# PiHAT_SSR_V4.net
KiCad netlist of a schematic drawn in EAGLE
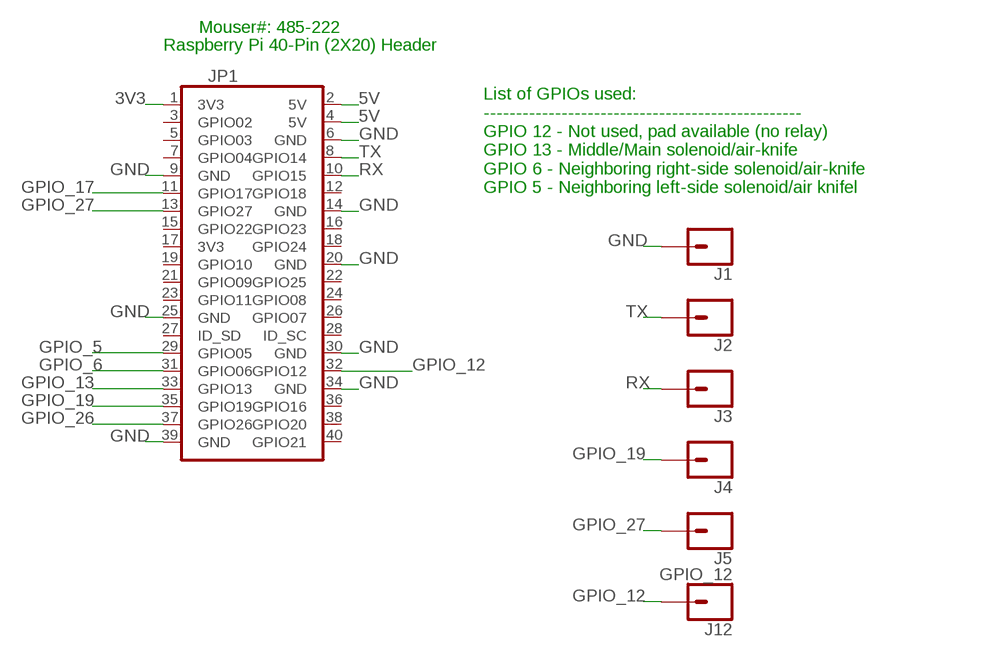
[diagram p0: schematic, sheet 1]
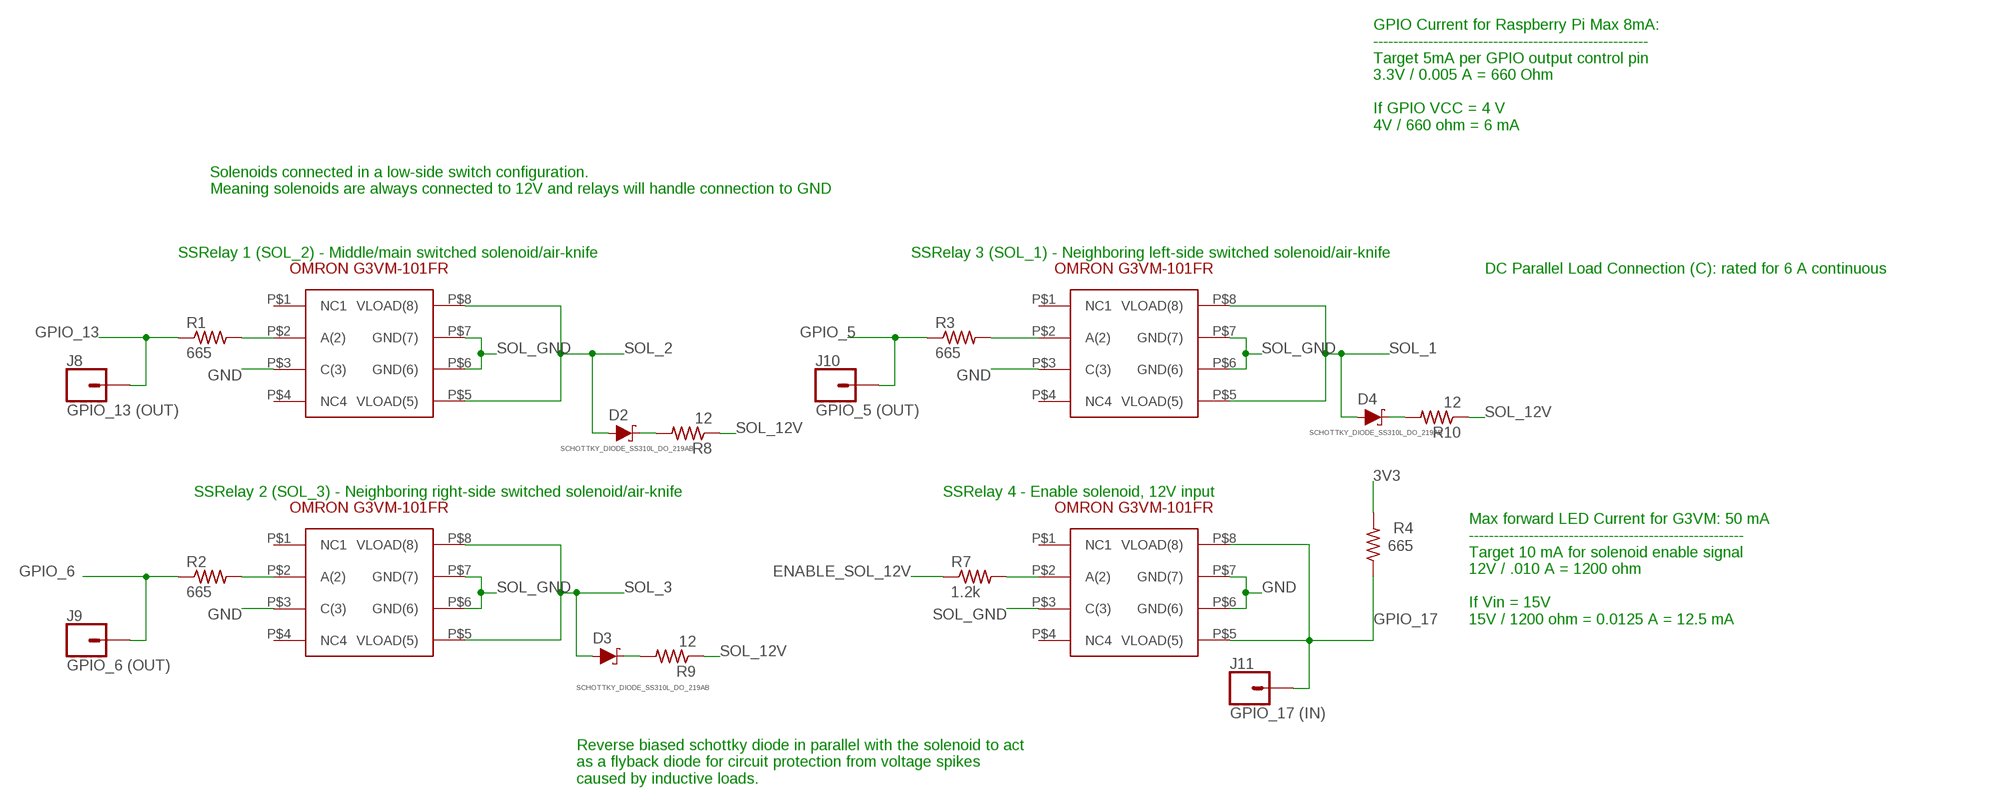
[diagram p1: schematic, sheet 2]
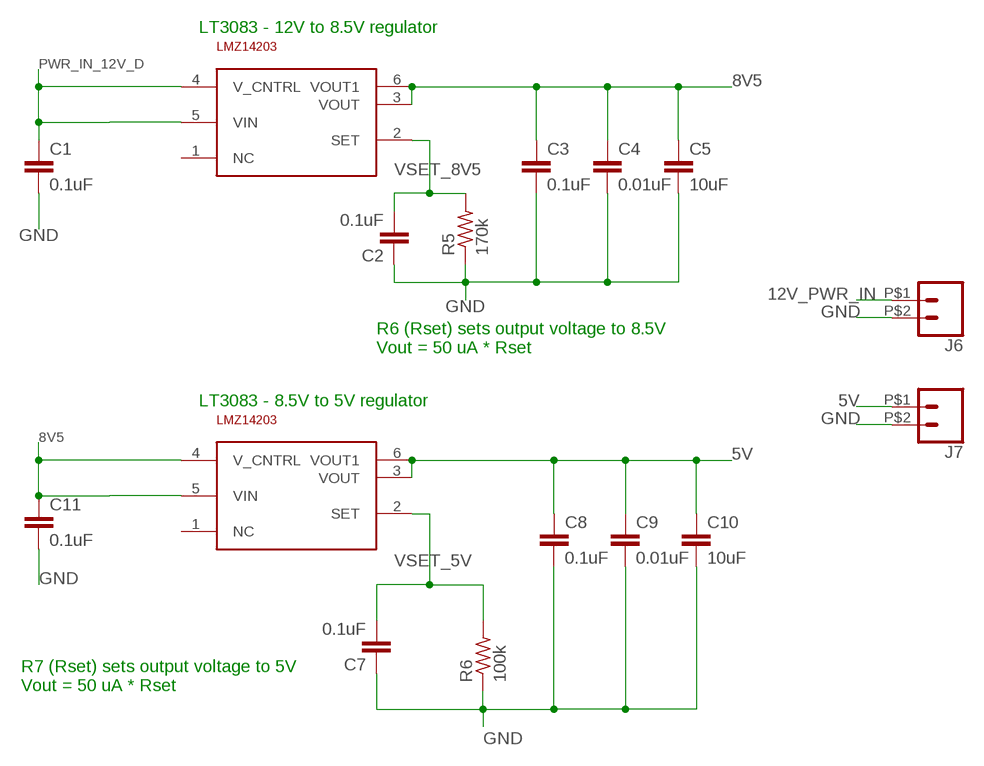
[diagram p2: schematic, sheet 3]
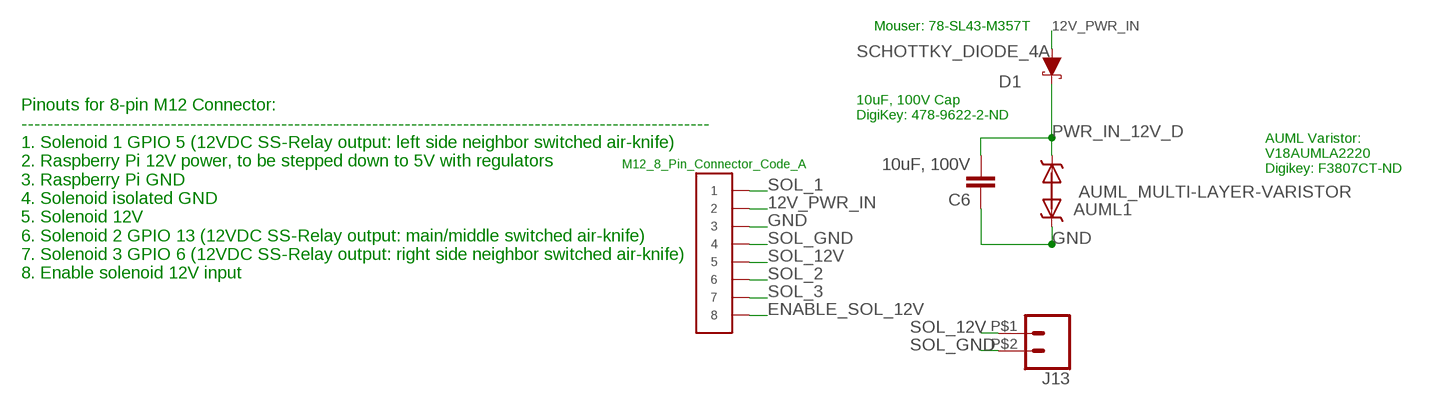
[diagram p3: schematic, sheet 4]

(export (version "E")
  (design (tool "Eeschema 10.0.6"))
  (components
    (comp (ref "C1")
      (value "0.1uF")
      (footprint "eagle-import:C0805")
      (libsource (lib "eagle-import") (part "C-EUC0805"))
    )
    (comp (ref "C2")
      (value "0.1uF")
      (footprint "eagle-import:C0805")
      (libsource (lib "eagle-import") (part "C-EUC0805"))
    )
    (comp (ref "C3")
      (value "0.1uF")
      (footprint "eagle-import:C0805")
      (libsource (lib "eagle-import") (part "C-EUC0805"))
    )
    (comp (ref "C4")
      (value "0.01uF")
      (footprint "eagle-import:C0805")
      (libsource (lib "eagle-import") (part "C-EUC0805"))
    )
    (comp (ref "C5")
      (value "10uF")
      (footprint "eagle-import:C0805")
      (libsource (lib "eagle-import") (part "C-EUC0805"))
    )
    (comp (ref "C7")
      (value "0.1uF")
      (footprint "eagle-import:C0805")
      (libsource (lib "eagle-import") (part "C-EUC0805"))
    )
    (comp (ref "C8")
      (value "0.1uF")
      (footprint "eagle-import:C0805")
      (libsource (lib "eagle-import") (part "C-EUC0805"))
    )
    (comp (ref "C9")
      (value "0.01uF")
      (footprint "eagle-import:C0805")
      (libsource (lib "eagle-import") (part "C-EUC0805"))
    )
    (comp (ref "C10")
      (value "10uF")
      (footprint "eagle-import:C0805")
      (libsource (lib "eagle-import") (part "C-EUC0805"))
    )
    (comp (ref "C11")
      (value "0.1uF")
      (footprint "eagle-import:C0805")
      (libsource (lib "eagle-import") (part "C-EUC0805"))
    )
    (comp (ref "J6")
      (value "CONN_02PTH2")
      (footprint "eagle-import:1X02_BIG")
      (libsource (lib "eagle-import") (part "CONN_02PTH2"))
    )
    (comp (ref "J7")
      (value "CONN_02PTH2")
      (footprint "eagle-import:1X02_BIG")
      (libsource (lib "eagle-import") (part "CONN_02PTH2"))
    )
    (comp (ref "R5")
      (value "170k")
      (footprint "eagle-import:M0805")
      (libsource (lib "eagle-import") (part "R-US_M0805"))
    )
    (comp (ref "R6")
      (value "100k")
      (footprint "eagle-import:M0805")
      (libsource (lib "eagle-import") (part "R-US_M0805"))
    )
    (comp (ref "VR1")
      (value "SMD-SPECIAL_28PIN_PIC32_11_3_2011_LT3083")
      (footprint "eagle-import:SMD-SPECIAL_28PIN_PIC32_11_3_2011_DPAK-5")
      (libsource (lib "eagle-import") (part "SMD-SPECIAL_28PIN_PIC32_11_3_2011_LT3083"))
    )
    (comp (ref "VR2")
      (value "SMD-SPECIAL_28PIN_PIC32_11_3_2011_LT3083")
      (footprint "eagle-import:SMD-SPECIAL_28PIN_PIC32_11_3_2011_DPAK-5")
      (libsource (lib "eagle-import") (part "SMD-SPECIAL_28PIN_PIC32_11_3_2011_LT3083"))
    )
    (comp (ref "J1")
      (value "CONN_01")
      (footprint "eagle-import:1X01")
      (libsource (lib "eagle-import") (part "CONN_01"))
    )
    (comp (ref "J2")
      (value "CONN_01")
      (footprint "eagle-import:1X01")
      (libsource (lib "eagle-import") (part "CONN_01"))
    )
    (comp (ref "J3")
      (value "CONN_01")
      (footprint "eagle-import:1X01")
      (libsource (lib "eagle-import") (part "CONN_01"))
    )
    (comp (ref "J4")
      (value "CONN_01")
      (footprint "eagle-import:1X01")
      (libsource (lib "eagle-import") (part "CONN_01"))
    )
    (comp (ref "J5")
      (value "CONN_01")
      (footprint "eagle-import:1X01")
      (libsource (lib "eagle-import") (part "CONN_01"))
    )
    (comp (ref "J12")
      (value "GPIO_12")
      (footprint "eagle-import:1X01")
      (libsource (lib "eagle-import") (part "CONN_01"))
    )
    (comp (ref "JP1")
      (value "40W_PI_HAT_TPH")
      (footprint "eagle-import:2X20")
      (libsource (lib "eagle-import") (part "40W_PI_HAT_TPH"))
    )
    (comp (ref "D2")
      (value "SCHOTTKY_DIODE_SS310L_DO_219AB")
      (footprint "eagle-import:SCHOTTKY_DIODE_DO219AB")
      (libsource (lib "eagle-import") (part "SCHOTTKY_DIODE_SS310L_DO_219AB"))
    )
    (comp (ref "D3")
      (value "SCHOTTKY_DIODE_SS310L_DO_219AB")
      (footprint "eagle-import:SCHOTTKY_DIODE_DO219AB")
      (libsource (lib "eagle-import") (part "SCHOTTKY_DIODE_SS310L_DO_219AB"))
    )
    (comp (ref "D4")
      (value "SCHOTTKY_DIODE_SS310L_DO_219AB")
      (footprint "eagle-import:SCHOTTKY_DIODE_DO219AB")
      (libsource (lib "eagle-import") (part "SCHOTTKY_DIODE_SS310L_DO_219AB"))
    )
    (comp (ref "J8")
      (value "GPIO_13 (OUT)")
      (footprint "eagle-import:1X01")
      (libsource (lib "eagle-import") (part "CONN_01"))
    )
    (comp (ref "J9")
      (value "GPIO_6 (OUT)")
      (footprint "eagle-import:1X01")
      (libsource (lib "eagle-import") (part "CONN_01"))
    )
    (comp (ref "J10")
      (value "GPIO_5 (OUT)")
      (footprint "eagle-import:1X01")
      (libsource (lib "eagle-import") (part "CONN_01"))
    )
    (comp (ref "J11")
      (value "GPIO_17 (IN)")
      (footprint "eagle-import:1X01")
      (libsource (lib "eagle-import") (part "CONN_01"))
    )
    (comp (ref "R1")
      (value "665")
      (footprint "eagle-import:M0805")
      (libsource (lib "eagle-import") (part "R-US_M0805"))
    )
    (comp (ref "R2")
      (value "665")
      (footprint "eagle-import:M0805")
      (libsource (lib "eagle-import") (part "R-US_M0805"))
    )
    (comp (ref "R3")
      (value "665")
      (footprint "eagle-import:M0805")
      (libsource (lib "eagle-import") (part "R-US_M0805"))
    )
    (comp (ref "R4")
      (value "665")
      (footprint "eagle-import:M0805")
      (libsource (lib "eagle-import") (part "R-US_M0805"))
    )
    (comp (ref "R7")
      (value "1.2k")
      (footprint "eagle-import:M0805")
      (libsource (lib "eagle-import") (part "R-US_M0805"))
    )
    (comp (ref "R8")
      (value "12")
      (footprint "eagle-import:R1210")
      (libsource (lib "eagle-import") (part "R-US_R1210"))
    )
    (comp (ref "R9")
      (value "12")
      (footprint "eagle-import:R1210")
      (libsource (lib "eagle-import") (part "R-US_R1210"))
    )
    (comp (ref "R10")
      (value "12")
      (footprint "eagle-import:R1210")
      (libsource (lib "eagle-import") (part "R-US_R1210"))
    )
    (comp (ref "SSR1")
      (value "OMRON_G3VM_101FR")
      (footprint "eagle-import:OMRON_G3VM-101FR")
      (libsource (lib "eagle-import") (part "OMRON_G3VM_101FR"))
    )
    (comp (ref "SSR2")
      (value "OMRON_G3VM_101FR")
      (footprint "eagle-import:OMRON_G3VM-101FR")
      (libsource (lib "eagle-import") (part "OMRON_G3VM_101FR"))
    )
    (comp (ref "SSR3")
      (value "OMRON_G3VM_101FR")
      (footprint "eagle-import:OMRON_G3VM-101FR")
      (libsource (lib "eagle-import") (part "OMRON_G3VM_101FR"))
    )
    (comp (ref "SSR4")
      (value "OMRON_G3VM_101FR")
      (footprint "eagle-import:OMRON_G3VM-101FR")
      (libsource (lib "eagle-import") (part "OMRON_G3VM_101FR"))
    )
    (comp (ref "AUML1")
      (value "SMD-SPECIAL_28PIN_PIC32_11_3_2011_MOD5_20_13_AUML_MULTI-LAYER-VARISTOR")
      (footprint "eagle-import:SMD-SPECIAL_28PIN_PIC32_11_3_2011_MOD5_20_13_SMT_CAP_2220")
      (libsource (lib "eagle-import") (part "SMD-SPECIAL_28PIN_PIC32_11_3_2011_MOD5_20_13_AUML_MULTI-LAYER-VARISTOR"))
    )
    (comp (ref "C6")
      (value "10uF, 100V")
      (footprint "eagle-import:C2220K")
      (libsource (lib "eagle-import") (part "C-EUC2220K"))
    )
    (comp (ref "CN1")
      (value "M12_8PIN_CODE_A")
      (footprint "eagle-import:M12_8PIN_CODE_A")
      (libsource (lib "eagle-import") (part "M12_8PIN_CODE_A"))
    )
    (comp (ref "D1")
      (value "SCHOTTKY_DIODE_4A")
      (footprint "eagle-import:SCHOTTKY_DIODE_SMD_DO-214AB")
      (libsource (lib "eagle-import") (part "SCHOTTKY_DIODE_4A"))
    )
    (comp (ref "J13")
      (value "CONN_02PTH2")
      (footprint "eagle-import:1X02_BIG")
      (libsource (lib "eagle-import") (part "CONN_02PTH2"))
    )
  )
  (nets
    (net (code "1") (name "3V3") (class "Default")
      (node (ref "JP1") (pin "1") (pinfunction "3V3_1") (pintype "passive"))
      (node (ref "R4") (pin "2") (pinfunction "2_2") (pintype "passive"))
    )
    (net (code "2") (name "5V") (class "Default")
      (node (ref "C10") (pin "1") (pinfunction "1_1") (pintype "passive"))
      (node (ref "C8") (pin "1") (pinfunction "1_1") (pintype "passive"))
      (node (ref "C9") (pin "1") (pinfunction "1_1") (pintype "passive"))
      (node (ref "J7") (pin "P$1") (pinfunction "1_P$1") (pintype "passive"))
      (node (ref "JP1") (pin "2") (pinfunction "5V_2") (pintype "passive"))
      (node (ref "JP1") (pin "4") (pinfunction "5V_4") (pintype "passive"))
      (node (ref "VR2") (pin "3") (pinfunction "VOUT_3") (pintype "bidirectional"))
      (node (ref "VR2") (pin "6") (pinfunction "VOUT1_6") (pintype "bidirectional"))
    )
    (net (code "3") (name "8V5") (class "Default")
      (node (ref "C11") (pin "1") (pinfunction "1_1") (pintype "passive"))
      (node (ref "C3") (pin "1") (pinfunction "1_1") (pintype "passive"))
      (node (ref "C4") (pin "1") (pinfunction "1_1") (pintype "passive"))
      (node (ref "C5") (pin "1") (pinfunction "1_1") (pintype "passive"))
      (node (ref "VR1") (pin "3") (pinfunction "VOUT_3") (pintype "bidirectional"))
      (node (ref "VR1") (pin "6") (pinfunction "VOUT1_6") (pintype "bidirectional"))
      (node (ref "VR2") (pin "4") (pinfunction "V_CNTRL_4") (pintype "bidirectional"))
      (node (ref "VR2") (pin "5") (pinfunction "VIN_5") (pintype "bidirectional"))
    )
    (net (code "4") (name "12V_PWR_IN") (class "Default")
      (node (ref "CN1") (pin "P$2") (pinfunction "P$2_P$2") (pintype "bidirectional"))
      (node (ref "D1") (pin "P$2") (pinfunction "A_P$2") (pintype "passive"))
      (node (ref "J6") (pin "P$1") (pinfunction "1_P$1") (pintype "passive"))
    )
    (net (code "5") (name "ENABLE_SOL_12V") (class "Default")
      (node (ref "CN1") (pin "P$8") (pinfunction "P$8_P$8") (pintype "bidirectional"))
      (node (ref "R7") (pin "1") (pinfunction "1_1") (pintype "passive"))
    )
    (net (code "6") (name "GND") (class "Default")
      (node (ref "AUML1") (pin "1") (pinfunction "1_1") (pintype "passive"))
      (node (ref "C1") (pin "2") (pinfunction "2_2") (pintype "passive"))
      (node (ref "C10") (pin "2") (pinfunction "2_2") (pintype "passive"))
      (node (ref "C11") (pin "2") (pinfunction "2_2") (pintype "passive"))
      (node (ref "C2") (pin "1") (pinfunction "1_1") (pintype "passive"))
      (node (ref "C3") (pin "2") (pinfunction "2_2") (pintype "passive"))
      (node (ref "C4") (pin "2") (pinfunction "2_2") (pintype "passive"))
      (node (ref "C5") (pin "2") (pinfunction "2_2") (pintype "passive"))
      (node (ref "C6") (pin "1") (pinfunction "1_1") (pintype "passive"))
      (node (ref "C7") (pin "1") (pinfunction "1_1") (pintype "passive"))
      (node (ref "C8") (pin "2") (pinfunction "2_2") (pintype "passive"))
      (node (ref "C9") (pin "2") (pinfunction "2_2") (pintype "passive"))
      (node (ref "CN1") (pin "P$3") (pinfunction "P$3_P$3") (pintype "bidirectional"))
      (node (ref "J1") (pin "1") (pinfunction "1_1") (pintype "passive"))
      (node (ref "J6") (pin "P$2") (pinfunction "2_P$2") (pintype "passive"))
      (node (ref "J7") (pin "P$2") (pinfunction "2_P$2") (pintype "passive"))
      (node (ref "JP1") (pin "14") (pinfunction "GND_14") (pintype "passive"))
      (node (ref "JP1") (pin "20") (pinfunction "GND_20") (pintype "passive"))
      (node (ref "JP1") (pin "25") (pinfunction "GND_25") (pintype "passive"))
      (node (ref "JP1") (pin "30") (pinfunction "GND_30") (pintype "passive"))
      (node (ref "JP1") (pin "34") (pinfunction "GND_34") (pintype "passive"))
      (node (ref "JP1") (pin "39") (pinfunction "GND_39") (pintype "passive"))
      (node (ref "JP1") (pin "6") (pinfunction "GND_6") (pintype "passive"))
      (node (ref "JP1") (pin "9") (pinfunction "GND_9") (pintype "passive"))
      (node (ref "R5") (pin "1") (pinfunction "1_1") (pintype "passive"))
      (node (ref "R6") (pin "1") (pinfunction "1_1") (pintype "passive"))
      (node (ref "SSR1") (pin "P$3") (pinfunction "C(3)_P$3") (pintype "bidirectional"))
      (node (ref "SSR2") (pin "P$3") (pinfunction "C(3)_P$3") (pintype "bidirectional"))
      (node (ref "SSR3") (pin "P$3") (pinfunction "C(3)_P$3") (pintype "bidirectional"))
      (node (ref "SSR4") (pin "P$6") (pinfunction "GND(6)_P$6") (pintype "bidirectional"))
      (node (ref "SSR4") (pin "P$7") (pinfunction "GND(7)_P$7") (pintype "bidirectional"))
    )
    (net (code "7") (name "GPIO_5") (class "Default")
      (node (ref "J10") (pin "1") (pinfunction "1_1") (pintype "passive"))
      (node (ref "JP1") (pin "29") (pinfunction "GPIO05_29") (pintype "passive"))
      (node (ref "R3") (pin "1") (pinfunction "1_1") (pintype "passive"))
    )
    (net (code "8") (name "GPIO_6") (class "Default")
      (node (ref "J9") (pin "1") (pinfunction "1_1") (pintype "passive"))
      (node (ref "JP1") (pin "31") (pinfunction "GPIO06_31") (pintype "passive"))
      (node (ref "R2") (pin "1") (pinfunction "1_1") (pintype "passive"))
    )
    (net (code "9") (name "GPIO_12") (class "Default")
      (node (ref "J12") (pin "1") (pinfunction "1_1") (pintype "passive"))
      (node (ref "JP1") (pin "32") (pinfunction "GPIO12_32") (pintype "passive"))
    )
    (net (code "10") (name "GPIO_13") (class "Default")
      (node (ref "J8") (pin "1") (pinfunction "1_1") (pintype "passive"))
      (node (ref "JP1") (pin "33") (pinfunction "GPIO13_33") (pintype "passive"))
      (node (ref "R1") (pin "1") (pinfunction "1_1") (pintype "passive"))
    )
    (net (code "11") (name "GPIO_17") (class "Default")
      (node (ref "J11") (pin "1") (pinfunction "1_1") (pintype "passive"))
      (node (ref "JP1") (pin "11") (pinfunction "GPIO17_11") (pintype "passive"))
      (node (ref "R4") (pin "1") (pinfunction "1_1") (pintype "passive"))
      (node (ref "SSR4") (pin "P$5") (pinfunction "VLOAD(5)_P$5") (pintype "bidirectional"))
      (node (ref "SSR4") (pin "P$8") (pinfunction "VLOAD(8)_P$8") (pintype "bidirectional"))
    )
    (net (code "12") (name "GPIO_19") (class "Default")
      (node (ref "J4") (pin "1") (pinfunction "1_1") (pintype "passive"))
      (node (ref "JP1") (pin "35") (pinfunction "GPIO19_35") (pintype "passive"))
    )
    (net (code "13") (name "GPIO_26") (class "Default")
      (node (ref "JP1") (pin "37") (pinfunction "GPIO26_37") (pintype "passive"))
    )
    (net (code "14") (name "GPIO_27") (class "Default")
      (node (ref "J5") (pin "1") (pinfunction "1_1") (pintype "passive"))
      (node (ref "JP1") (pin "13") (pinfunction "GPIO27_13") (pintype "passive"))
    )
    (net (code "15") (name "Net-(D2-C)") (class "Default")
      (node (ref "D2") (pin "P$2") (pinfunction "C_P$2") (pintype "passive"))
      (node (ref "R8") (pin "2") (pinfunction "2_2") (pintype "passive"))
    )
    (net (code "16") (name "Net-(D3-C)") (class "Default")
      (node (ref "D3") (pin "P$2") (pinfunction "C_P$2") (pintype "passive"))
      (node (ref "R9") (pin "2") (pinfunction "2_2") (pintype "passive"))
    )
    (net (code "17") (name "Net-(D4-C)") (class "Default")
      (node (ref "D4") (pin "P$2") (pinfunction "C_P$2") (pintype "passive"))
      (node (ref "R10") (pin "2") (pinfunction "2_2") (pintype "passive"))
    )
    (net (code "18") (name "Net-(SSR1-A(2))") (class "Default")
      (node (ref "R1") (pin "2") (pinfunction "2_2") (pintype "passive"))
      (node (ref "SSR1") (pin "P$2") (pinfunction "A(2)_P$2") (pintype "bidirectional"))
    )
    (net (code "19") (name "Net-(SSR2-A(2))") (class "Default")
      (node (ref "R2") (pin "2") (pinfunction "2_2") (pintype "passive"))
      (node (ref "SSR2") (pin "P$2") (pinfunction "A(2)_P$2") (pintype "bidirectional"))
    )
    (net (code "20") (name "Net-(SSR3-A(2))") (class "Default")
      (node (ref "R3") (pin "2") (pinfunction "2_2") (pintype "passive"))
      (node (ref "SSR3") (pin "P$2") (pinfunction "A(2)_P$2") (pintype "bidirectional"))
    )
    (net (code "21") (name "Net-(SSR4-A(2))") (class "Default")
      (node (ref "R7") (pin "2") (pinfunction "2_2") (pintype "passive"))
      (node (ref "SSR4") (pin "P$2") (pinfunction "A(2)_P$2") (pintype "bidirectional"))
    )
    (net (code "22") (name "PWR_IN_12V_D") (class "Default")
      (node (ref "AUML1") (pin "2") (pinfunction "2_2") (pintype "passive"))
      (node (ref "C1") (pin "1") (pinfunction "1_1") (pintype "passive"))
      (node (ref "C6") (pin "2") (pinfunction "2_2") (pintype "passive"))
      (node (ref "D1") (pin "P$1") (pinfunction "C_P$1") (pintype "passive"))
      (node (ref "VR1") (pin "4") (pinfunction "V_CNTRL_4") (pintype "bidirectional"))
      (node (ref "VR1") (pin "5") (pinfunction "VIN_5") (pintype "bidirectional"))
    )
    (net (code "23") (name "RX") (class "Default")
      (node (ref "J3") (pin "1") (pinfunction "1_1") (pintype "passive"))
      (node (ref "JP1") (pin "10") (pinfunction "GPIO15_10") (pintype "passive"))
    )
    (net (code "24") (name "SOL_1") (class "Default")
      (node (ref "CN1") (pin "P$1") (pinfunction "P$1_P$1") (pintype "bidirectional"))
      (node (ref "D4") (pin "P$1") (pinfunction "A_P$1") (pintype "passive"))
      (node (ref "SSR3") (pin "P$5") (pinfunction "VLOAD(5)_P$5") (pintype "bidirectional"))
      (node (ref "SSR3") (pin "P$8") (pinfunction "VLOAD(8)_P$8") (pintype "bidirectional"))
    )
    (net (code "25") (name "SOL_2") (class "Default")
      (node (ref "CN1") (pin "P$6") (pinfunction "P$6_P$6") (pintype "bidirectional"))
      (node (ref "D2") (pin "P$1") (pinfunction "A_P$1") (pintype "passive"))
      (node (ref "SSR1") (pin "P$5") (pinfunction "VLOAD(5)_P$5") (pintype "bidirectional"))
      (node (ref "SSR1") (pin "P$8") (pinfunction "VLOAD(8)_P$8") (pintype "bidirectional"))
    )
    (net (code "26") (name "SOL_3") (class "Default")
      (node (ref "CN1") (pin "P$7") (pinfunction "P$7_P$7") (pintype "bidirectional"))
      (node (ref "D3") (pin "P$1") (pinfunction "A_P$1") (pintype "passive"))
      (node (ref "SSR2") (pin "P$5") (pinfunction "VLOAD(5)_P$5") (pintype "bidirectional"))
      (node (ref "SSR2") (pin "P$8") (pinfunction "VLOAD(8)_P$8") (pintype "bidirectional"))
    )
    (net (code "27") (name "SOL_12V") (class "Default")
      (node (ref "CN1") (pin "P$5") (pinfunction "P$5_P$5") (pintype "bidirectional"))
      (node (ref "J13") (pin "P$1") (pinfunction "1_P$1") (pintype "passive"))
      (node (ref "R10") (pin "1") (pinfunction "1_1") (pintype "passive"))
      (node (ref "R8") (pin "1") (pinfunction "1_1") (pintype "passive"))
      (node (ref "R9") (pin "1") (pinfunction "1_1") (pintype "passive"))
    )
    (net (code "28") (name "SOL_GND") (class "Default")
      (node (ref "CN1") (pin "P$4") (pinfunction "P$4_P$4") (pintype "bidirectional"))
      (node (ref "J13") (pin "P$2") (pinfunction "2_P$2") (pintype "passive"))
      (node (ref "SSR1") (pin "P$6") (pinfunction "GND(6)_P$6") (pintype "bidirectional"))
      (node (ref "SSR1") (pin "P$7") (pinfunction "GND(7)_P$7") (pintype "bidirectional"))
      (node (ref "SSR2") (pin "P$6") (pinfunction "GND(6)_P$6") (pintype "bidirectional"))
      (node (ref "SSR2") (pin "P$7") (pinfunction "GND(7)_P$7") (pintype "bidirectional"))
      (node (ref "SSR3") (pin "P$6") (pinfunction "GND(6)_P$6") (pintype "bidirectional"))
      (node (ref "SSR3") (pin "P$7") (pinfunction "GND(7)_P$7") (pintype "bidirectional"))
      (node (ref "SSR4") (pin "P$3") (pinfunction "C(3)_P$3") (pintype "bidirectional"))
    )
    (net (code "29") (name "TX") (class "Default")
      (node (ref "J2") (pin "1") (pinfunction "1_1") (pintype "passive"))
      (node (ref "JP1") (pin "8") (pinfunction "GPIO14_8") (pintype "passive"))
    )
    (net (code "30") (name "VSET_5V") (class "Default")
      (node (ref "C7") (pin "2") (pinfunction "2_2") (pintype "passive"))
      (node (ref "R6") (pin "2") (pinfunction "2_2") (pintype "passive"))
      (node (ref "VR2") (pin "2") (pinfunction "SET_2") (pintype "bidirectional"))
    )
    (net (code "31") (name "VSET_8V5") (class "Default")
      (node (ref "C2") (pin "2") (pinfunction "2_2") (pintype "passive"))
      (node (ref "R5") (pin "2") (pinfunction "2_2") (pintype "passive"))
      (node (ref "VR1") (pin "2") (pinfunction "SET_2") (pintype "bidirectional"))
    )
    (net (code "32") (name "unconnected-(JP1-3V3-Pad17)") (class "Default")
      (node (ref "JP1") (pin "17") (pinfunction "3V3_17") (pintype "passive"))
    )
    (net (code "33") (name "unconnected-(JP1-GPIO02-Pad3)") (class "Default")
      (node (ref "JP1") (pin "3") (pinfunction "GPIO02_3") (pintype "passive"))
    )
    (net (code "34") (name "unconnected-(JP1-GPIO03-Pad5)") (class "Default")
      (node (ref "JP1") (pin "5") (pinfunction "GPIO03_5") (pintype "passive"))
    )
    (net (code "35") (name "unconnected-(JP1-GPIO04-Pad7)") (class "Default")
      (node (ref "JP1") (pin "7") (pinfunction "GPIO04_7") (pintype "passive"))
    )
    (net (code "36") (name "unconnected-(JP1-GPIO07-Pad26)") (class "Default")
      (node (ref "JP1") (pin "26") (pinfunction "GPIO07_26") (pintype "passive"))
    )
    (net (code "37") (name "unconnected-(JP1-GPIO08-Pad24)") (class "Default")
      (node (ref "JP1") (pin "24") (pinfunction "GPIO08_24") (pintype "passive"))
    )
    (net (code "38") (name "unconnected-(JP1-GPIO09-Pad21)") (class "Default")
      (node (ref "JP1") (pin "21") (pinfunction "GPIO09_21") (pintype "passive"))
    )
    (net (code "39") (name "unconnected-(JP1-GPIO10-Pad19)") (class "Default")
      (node (ref "JP1") (pin "19") (pinfunction "GPIO10_19") (pintype "passive"))
    )
    (net (code "40") (name "unconnected-(JP1-GPIO11-Pad23)") (class "Default")
      (node (ref "JP1") (pin "23") (pinfunction "GPIO11_23") (pintype "passive"))
    )
    (net (code "41") (name "unconnected-(JP1-GPIO16-Pad36)") (class "Default")
      (node (ref "JP1") (pin "36") (pinfunction "GPIO16_36") (pintype "passive"))
    )
    (net (code "42") (name "unconnected-(JP1-GPIO18-Pad12)") (class "Default")
      (node (ref "JP1") (pin "12") (pinfunction "GPIO18_12") (pintype "passive"))
    )
    (net (code "43") (name "unconnected-(JP1-GPIO20-Pad38)") (class "Default")
      (node (ref "JP1") (pin "38") (pinfunction "GPIO20_38") (pintype "passive"))
    )
    (net (code "44") (name "unconnected-(JP1-GPIO21-Pad40)") (class "Default")
      (node (ref "JP1") (pin "40") (pinfunction "GPIO21_40") (pintype "passive"))
    )
    (net (code "45") (name "unconnected-(JP1-GPIO22-Pad15)") (class "Default")
      (node (ref "JP1") (pin "15") (pinfunction "GPIO22_15") (pintype "passive"))
    )
    (net (code "46") (name "unconnected-(JP1-GPIO23-Pad16)") (class "Default")
      (node (ref "JP1") (pin "16") (pinfunction "GPIO23_16") (pintype "passive"))
    )
    (net (code "47") (name "unconnected-(JP1-GPIO24-Pad18)") (class "Default")
      (node (ref "JP1") (pin "18") (pinfunction "GPIO24_18") (pintype "passive"))
    )
    (net (code "48") (name "unconnected-(JP1-GPIO25-Pad22)") (class "Default")
      (node (ref "JP1") (pin "22") (pinfunction "GPIO25_22") (pintype "passive"))
    )
    (net (code "49") (name "unconnected-(JP1-ID_SC-Pad28)") (class "Default")
      (node (ref "JP1") (pin "28") (pinfunction "ID_SC_28") (pintype "passive"))
    )
    (net (code "50") (name "unconnected-(JP1-ID_SD-Pad27)") (class "Default")
      (node (ref "JP1") (pin "27") (pinfunction "ID_SD_27") (pintype "passive"))
    )
    (net (code "51") (name "unconnected-(SSR1-NC1-PadP$1)") (class "Default")
      (node (ref "SSR1") (pin "P$1") (pinfunction "NC1_P$1") (pintype "bidirectional"))
    )
    (net (code "52") (name "unconnected-(SSR1-NC4-PadP$4)") (class "Default")
      (node (ref "SSR1") (pin "P$4") (pinfunction "NC4_P$4") (pintype "bidirectional"))
    )
    (net (code "53") (name "unconnected-(SSR2-NC1-PadP$1)") (class "Default")
      (node (ref "SSR2") (pin "P$1") (pinfunction "NC1_P$1") (pintype "bidirectional"))
    )
    (net (code "54") (name "unconnected-(SSR2-NC4-PadP$4)") (class "Default")
      (node (ref "SSR2") (pin "P$4") (pinfunction "NC4_P$4") (pintype "bidirectional"))
    )
    (net (code "55") (name "unconnected-(SSR3-NC1-PadP$1)") (class "Default")
      (node (ref "SSR3") (pin "P$1") (pinfunction "NC1_P$1") (pintype "bidirectional"))
    )
    (net (code "56") (name "unconnected-(SSR3-NC4-PadP$4)") (class "Default")
      (node (ref "SSR3") (pin "P$4") (pinfunction "NC4_P$4") (pintype "bidirectional"))
    )
    (net (code "57") (name "unconnected-(SSR4-NC1-PadP$1)") (class "Default")
      (node (ref "SSR4") (pin "P$1") (pinfunction "NC1_P$1") (pintype "bidirectional"))
    )
    (net (code "58") (name "unconnected-(SSR4-NC4-PadP$4)") (class "Default")
      (node (ref "SSR4") (pin "P$4") (pinfunction "NC4_P$4") (pintype "bidirectional"))
    )
    (net (code "59") (name "unconnected-(VR1-NC-Pad1)") (class "Default")
      (node (ref "VR1") (pin "1") (pinfunction "NC_1") (pintype "bidirectional"))
    )
    (net (code "60") (name "unconnected-(VR2-NC-Pad1)") (class "Default")
      (node (ref "VR2") (pin "1") (pinfunction "NC_1") (pintype "bidirectional"))
    )
  )
)
